# Weathe_Station.net
KiCad netlist of a schematic drawn in Altium Designer
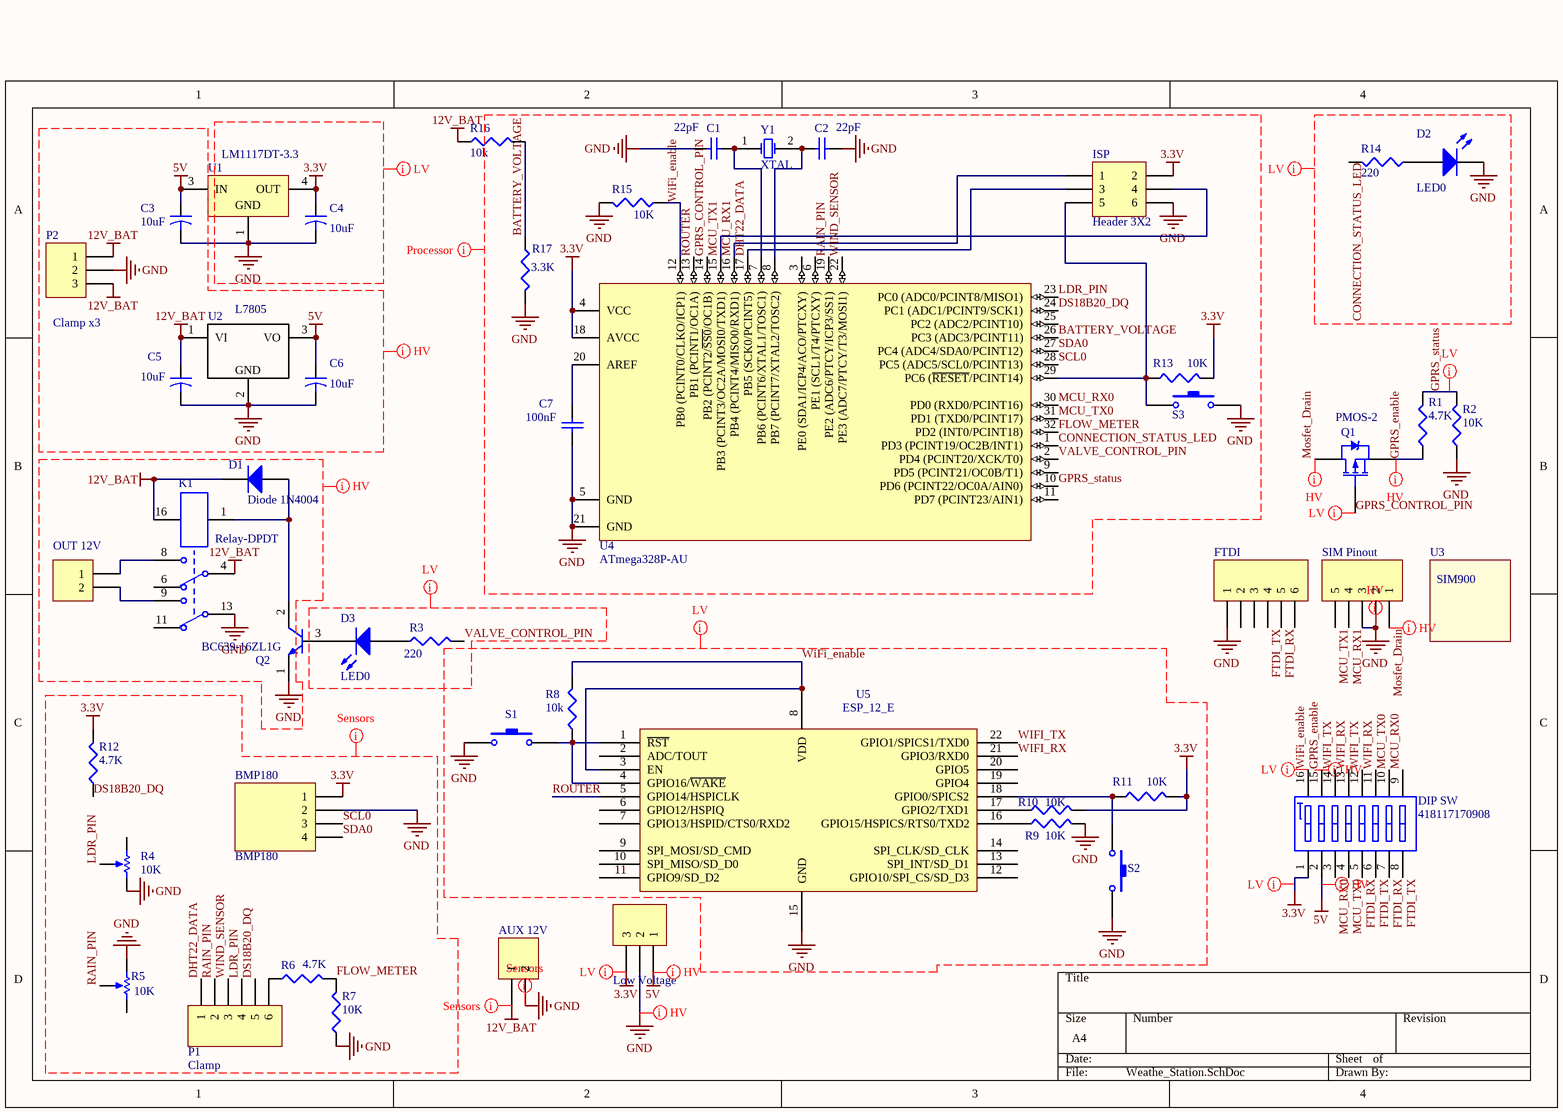
[diagram p0: Weathe_Station.SchDoc]

(export (version "E")
  (design (tool "Eeschema 10.0.6"))
  (components
    (comp (ref "AUX 12V")
      (value "AUX 12V")
      (footprint "Connector (Clamp?)")
      (description "Klema")
      (fields (field (name "PUBLISHER") "Altium Limited"))
      (libsource (lib "Connector_clamp") (part "Header 2"))
    )
    (comp (ref "BMP180")
      (value "BMP180")
      (footprint "BMP180")
      (fields (field (name "PUBLISHER") "Altium Limited"))
      (libsource (lib "BMP180") (part "BMP180"))
    )
    (comp (ref "C1")
      (value "22pF")
      (footprint "C1206")
      (description "Capacitor (Semiconductor SIM Model)")
      (fields (field (name "Comment") "Cap Semi") (field (name "PUBLISHER") "Altium Limited"))
      (libsource (lib "Miscellaneous Devices") (part "Cap Semi"))
    )
    (comp (ref "C2")
      (value "22pF")
      (footprint "C1206")
      (description "Capacitor (Semiconductor SIM Model)")
      (fields (field (name "Comment") "Cap Semi") (field (name "PUBLISHER") "Altium Limited"))
      (libsource (lib "Miscellaneous Devices") (part "Cap Semi"))
    )
    (comp (ref "C3")
      (value "10uF")
      (footprint "CAPR5-4X5")
      (description "Capacitor")
      (fields (field (name "Comment") "Cap2") (field (name "PUBLISHER") "Altium Limited"))
      (libsource (lib "Miscellaneous Devices") (part "Cap2"))
    )
    (comp (ref "C4")
      (value "10uF")
      (footprint "CAPR5-4X5")
      (description "Capacitor")
      (fields (field (name "Comment") "Cap2") (field (name "PUBLISHER") "Altium Limited"))
      (libsource (lib "Miscellaneous Devices") (part "Cap2"))
    )
    (comp (ref "C5")
      (value "10uF")
      (footprint "CAPR5-4X5")
      (description "Capacitor")
      (fields (field (name "Comment") "Cap2") (field (name "PUBLISHER") "Altium Limited"))
      (libsource (lib "Miscellaneous Devices") (part "Cap2"))
    )
    (comp (ref "C6")
      (value "10uF")
      (footprint "CAPR5-4X5")
      (description "Capacitor")
      (fields (field (name "Comment") "Cap2") (field (name "PUBLISHER") "Altium Limited"))
      (libsource (lib "Miscellaneous Devices") (part "Cap2"))
    )
    (comp (ref "C7")
      (value "100nF")
      (footprint "C1206")
      (description "Capacitor (Semiconductor SIM Model)")
      (fields (field (name "Comment") "Cap Semi") (field (name "PUBLISHER") "Altium Limited"))
      (libsource (lib "Miscellaneous Devices") (part "Cap Semi"))
    )
    (comp (ref "D1")
      (value "Diode 1N4004")
      (footprint "DO-41")
      (description "1 Amp General Purpose Rectifier")
      (fields (field (name "PUBLISHER") "Altium Limited"))
      (libsource (lib "Miscellaneous Devices") (part "Diode 1N4004"))
    )
    (comp (ref "D2")
      (value "LED0")
      (footprint "INDC3216")
      (description "SMD led")
      (fields (field (name "PUBLISHER") "Altium Limited"))
      (libsource (lib "SMD Led") (part "LED0"))
    )
    (comp (ref "D3")
      (value "LED0")
      (footprint "INDC3216")
      (description "SMD led")
      (fields (field (name "PUBLISHER") "Altium Limited"))
      (libsource (lib "SMD Led") (part "LED0"))
    )
    (comp (ref "DIP SW")
      (value "418117170908")
      (footprint "418117170908")
      (description "2.54 mm Compact THT Dip Switch with Flat Actuator WS-DITV")
      (libsource (lib "WS-DITV 2.54 mm Compact THT Dip Switch with Flat Actuator") (part "418117170908"))
    )
    (comp (ref "FTDI")
      (value "Header 6")
      (footprint "HDR1X6")
      (description "Header, 6-Pin")
      (fields (field (name "PUBLISHER") "Altium Limited"))
      (libsource (lib "Miscellaneous Connectors") (part "Header 6"))
    )
    (comp (ref "ISP")
      (value "Header 3X2")
      (footprint "HDR2X3")
      (description "Header, 3-Pin, Dual row")
      (fields (field (name "PUBLISHER") "Altium Limited"))
      (libsource (lib "Miscellaneous Connectors") (part "Header 3X2"))
    )
    (comp (ref "K1")
      (value "Relay-DPDT")
      (footprint "Sanyou Relay")
      (description "Dual-Pole Dual-Throw Relay")
      (fields (field (name "PUBLISHER") "Altium Limited"))
      (libsource (lib "Sanyou Relay") (part "Relay-DPDT"))
    )
    (comp (ref "Low Voltage")
      (value "Clamp x3")
      (footprint "Connector x3 clamps")
      (fields (field (name "PUBLISHER") "Altium Limited"))
      (libsource (lib "Connector_clamp_x3") (part "Clamp x3"))
    )
    (comp (ref "OUT 12V")
      (value "Homemade Connector")
      (footprint "Connector (Clamp?)")
      (description "Klema")
      (fields (field (name "PUBLISHER") "Altium Limited"))
      (libsource (lib "") (part "Header 2_1"))
    )
    (comp (ref "P1")
      (value "Clamp")
      (footprint "Connector Clamp (x6)")
      (description "Header, 6-Pin")
      (fields (field (name "PUBLISHER") "Altium Limited"))
      (libsource (lib "Connector_clamp_x6") (part "Header 6"))
    )
    (comp (ref "P2")
      (value "Clamp x3")
      (footprint "Connector x3 clamps")
      (fields (field (name "PUBLISHER") "Altium Limited"))
      (libsource (lib "") (part "Clamp x3_1"))
    )
    (comp (ref "Q1")
      (value "PMOS-2")
      (footprint "TO-220AB")
      (description "P-Channel Power MOSFET")
      (fields (field (name "PUBLISHER") "Altium Limited"))
      (libsource (lib "Miscellaneous Devices") (part "PMOS-2"))
    )
    (comp (ref "Q2")
      (value "BC639-16ZL1G")
      (footprint "ONSC-TO-92-3-29-11_AM_BL")
      (description "High Current Transistor, NPN Silicon, 3-Pin TO-92, Pb-Free, Ammo Box")
      (fields (field (name "MANUFACTURER") "On Semiconductor"))
      (libsource (lib "ON Semi General Purpose Transistors") (part "BC639-16ZL1G"))
    )
    (comp (ref "R1")
      (value "4.7K")
      (footprint "smd resistor 4x2mm")
      (fields (field (name "Comment") "smd resistor 4x2mm") (field (name "PUBLISHER") "Altium Limited"))
      (libsource (lib "smd resistor 4x2mm") (part "Res3"))
    )
    (comp (ref "R2")
      (value "10K")
      (footprint "smd resistor 4x2mm")
      (fields (field (name "Comment") "smd resistor 4x2mm") (field (name "PUBLISHER") "Altium Limited"))
      (libsource (lib "smd resistor 4x2mm") (part "Res3"))
    )
    (comp (ref "R3")
      (value "220")
      (footprint "smd resistor 4x2mm")
      (fields (field (name "Comment") "smd resistor 4x2mm") (field (name "PUBLISHER") "Altium Limited"))
      (libsource (lib "smd resistor 4x2mm") (part "Res3"))
    )
    (comp (ref "R4")
      (value "10K")
      (footprint "potentiometer (Piher)")
      (description "Potentiometer")
      (fields (field (name "Comment") "RPot") (field (name "PUBLISHER") "Altium Limited"))
      (libsource (lib "potentiometer (Piher)") (part "RPot"))
    )
    (comp (ref "R5")
      (value "10K")
      (footprint "potentiometer (Piher)")
      (description "Potentiometer")
      (fields (field (name "Comment") "RPot") (field (name "PUBLISHER") "Altium Limited"))
      (libsource (lib "potentiometer (Piher)") (part "RPot"))
    )
    (comp (ref "R6")
      (value "4.7K")
      (footprint "smd resistor 4x2mm")
      (fields (field (name "Comment") "smd resistor 4x2mm") (field (name "PUBLISHER") "Altium Limited"))
      (libsource (lib "smd resistor 4x2mm") (part "Res3"))
    )
    (comp (ref "R7")
      (value "10K")
      (footprint "smd resistor 4x2mm")
      (fields (field (name "Comment") "smd resistor 4x2mm") (field (name "PUBLISHER") "Altium Limited"))
      (libsource (lib "smd resistor 4x2mm") (part "Res3"))
    )
    (comp (ref "R8")
      (value "10k")
      (footprint "smd resistor 4x2mm")
      (fields (field (name "Comment") "smd resistor") (field (name "PUBLISHER") "Altium Limited"))
      (libsource (lib "smd resistor 4x2mm") (part "Res3"))
    )
    (comp (ref "R9")
      (value "10K")
      (footprint "smd resistor 4x2mm")
      (fields (field (name "Comment") "smd resistor 4x2mm") (field (name "PUBLISHER") "Altium Limited"))
      (libsource (lib "smd resistor 4x2mm") (part "Res3"))
    )
    (comp (ref "R10")
      (value "10K")
      (footprint "smd resistor 4x2mm")
      (fields (field (name "Comment") "smd resistor 4x2mm") (field (name "PUBLISHER") "Altium Limited"))
      (libsource (lib "smd resistor 4x2mm") (part "Res3"))
    )
    (comp (ref "R11")
      (value "10K")
      (footprint "smd resistor 4x2mm")
      (fields (field (name "Comment") "smd resistor 4x2mm") (field (name "PUBLISHER") "Altium Limited"))
      (libsource (lib "smd resistor 4x2mm") (part "Res3"))
    )
    (comp (ref "R12")
      (value "4.7K")
      (footprint "smd resistor 4x2mm")
      (fields (field (name "Comment") "smd resistor 4x2mm") (field (name "PUBLISHER") "Altium Limited"))
      (libsource (lib "smd resistor 4x2mm") (part "Res3"))
    )
    (comp (ref "R13")
      (value "10K")
      (footprint "smd resistor 4x2mm")
      (fields (field (name "Comment") "smd resistor 4x2mm") (field (name "PUBLISHER") "Altium Limited"))
      (libsource (lib "smd resistor 4x2mm") (part "Res3"))
    )
    (comp (ref "R14")
      (value "220")
      (footprint "smd resistor 4x2mm")
      (fields (field (name "Comment") "smd resistor 4x2mm") (field (name "PUBLISHER") "Altium Limited"))
      (libsource (lib "smd resistor 4x2mm") (part "Res3"))
    )
    (comp (ref "R15")
      (value "10K")
      (footprint "smd resistor 4x2mm")
      (fields (field (name "Comment") "smd resistor 4x2mm") (field (name "PUBLISHER") "Altium Limited"))
      (libsource (lib "smd resistor 4x2mm") (part "Res3"))
    )
    (comp (ref "R16")
      (value "10k")
      (footprint "smd resistor 4x2mm")
      (fields (field (name "Comment") "smd resistor 4x2mm") (field (name "PUBLISHER") "Altium Limited"))
      (libsource (lib "smd resistor 4x2mm") (part "Res3"))
    )
    (comp (ref "R17")
      (value "3.3K")
      (footprint "smd resistor 4x2mm")
      (fields (field (name "Comment") "smd resistor 4x2mm") (field (name "PUBLISHER") "Altium Limited"))
      (libsource (lib "smd resistor 4x2mm") (part "Res3"))
    )
    (comp (ref "S1")
      (value "SW-PB")
      (footprint "SMD push button 10x4")
      (description "Switch")
      (fields (field (name "PUBLISHER") "Altium Limited"))
      (libsource (lib "SMD push button 10x4") (part "SW-PB"))
    )
    (comp (ref "S2")
      (value "SW-PB")
      (footprint "SMD push button 10x4")
      (description "Switch")
      (fields (field (name "PUBLISHER") "Altium Limited"))
      (libsource (lib "SMD push button 10x4") (part "SW-PB"))
    )
    (comp (ref "S3")
      (value "SW-PB")
      (footprint "SMD push button 10x4")
      (description "Switch")
      (fields (field (name "PUBLISHER") "Altium Limited"))
      (libsource (lib "SMD push button 10x4") (part "SW-PB"))
    )
    (comp (ref "SIM Pinout")
      (value "Header 5")
      (footprint "HDR1X5")
      (description "Header, 5-Pin")
      (fields (field (name "PUBLISHER") "Altium Limited"))
      (libsource (lib "Miscellaneous Connectors") (part "Header 5"))
    )
    (comp (ref "U1")
      (value "LM1117DT-3.3")
      (footprint "TD03B_N")
      (description "800mA Low-Dropout Linear Regulator, 3-pin TO-252")
      (fields (field (name "MANUFACTURER") "National Semiconductor"))
      (libsource (lib "National Semiconductor LDO") (part "LM1117DT-3.3"))
    )
    (comp (ref "U2")
      (value "L7805")
      (footprint "D2PAK")
      (description "LINEAR REGULATOR 5.0V")
      (libsource (lib "vh_altium_library") (part "L7805-D2PAK"))
    )
    (comp (ref "U3") (value "SIM900") (footprint "SIM900") (libsource (lib "SIM900") (part "SIM900")))
    (comp (ref "U4")
      (value "ATmega328P-AU")
      (footprint "32A_L")
      (fields (field (name "PUBLISHER") "Altium Limited"))
      (libsource (lib "ATmega328PB") (part "ATmega328P-AU"))
    )
    (comp (ref "U5")
      (value "ESP_12_E")
      (footprint "ESP_12_E")
      (description "ESP-12 Wi-Fi Module by AI-Thinker")
      (libsource (lib "ESP8266") (part "ESP_12_E"))
    )
    (comp (ref "Y1")
      (value "XTAL")
      (footprint "R38")
      (description "Crystal Oscillator")
      (fields (field (name "PUBLISHER") "Altium Limited"))
      (libsource (lib "Miscellaneous Devices") (part "XTAL"))
    )
  )
  (nets
    (net (code "1") (name "/BATTERY_VOLTAGE") (class "Default")
      (node (ref "R16") (pin "2") (pinfunction "2_2") (pintype "passive"))
      (node (ref "R17") (pin "1") (pinfunction "1_1") (pintype "passive"))
      (node (ref "U4") (pin "26") (pinfunction "PC3_(ADC3/PCINT11)_26") (pintype "bidirectional"))
    )
    (net (code "2") (name "/CONNECTION_STATUS_LED") (class "Default")
      (node (ref "R14") (pin "2") (pinfunction "2_2") (pintype "passive"))
      (node (ref "U4") (pin "1") (pinfunction "PD3_(PCINT19/OC2B/INT1)_1") (pintype "bidirectional"))
    )
    (net (code "3") (name "/DHT22_DATA") (class "Default")
      (node (ref "ISP") (pin "3") (pinfunction "3_3") (pintype "passive"))
      (node (ref "P1") (pin "1") (pinfunction "1_1") (pintype "passive"))
      (node (ref "U4") (pin "17") (pinfunction "PB5_(SCK0/PCINT5)_17") (pintype "bidirectional"))
    )
    (net (code "4") (name "/DS18B20_DQ") (class "Default")
      (node (ref "P1") (pin "5") (pinfunction "5_5") (pintype "passive"))
      (node (ref "R12") (pin "1") (pinfunction "1_1") (pintype "passive"))
      (node (ref "U4") (pin "24") (pinfunction "PC1_(ADC1/PCINT9/SCK1)_24") (pintype "bidirectional"))
    )
    (net (code "5") (name "/FLOW_METER") (class "Default")
      (node (ref "R6") (pin "2") (pinfunction "2_2") (pintype "passive"))
      (node (ref "R7") (pin "2") (pinfunction "2_2") (pintype "passive"))
      (node (ref "U4") (pin "32") (pinfunction "PD2_(INT0/PCINT18)_32") (pintype "bidirectional"))
    )
    (net (code "6") (name "/FTDI_RX") (class "Default")
      (node (ref "DIP SW") (pin "5") (pinfunction "5_5") (pintype "passive"))
      (node (ref "DIP SW") (pin "7") (pinfunction "7_7") (pintype "passive"))
      (node (ref "FTDI") (pin "5") (pinfunction "5_5") (pintype "passive"))
    )
    (net (code "7") (name "/FTDI_TX") (class "Default")
      (node (ref "DIP SW") (pin "6") (pinfunction "6_6") (pintype "passive"))
      (node (ref "DIP SW") (pin "8") (pinfunction "8_8") (pintype "passive"))
      (node (ref "FTDI") (pin "4") (pinfunction "4_4") (pintype "passive"))
    )
    (net (code "8") (name "/GPRS_CONTROL_PIN") (class "Default")
      (node (ref "Q1") (pin "1") (pinfunction "G_1") (pintype "passive"))
      (node (ref "U4") (pin "14") (pinfunction "PB2_(PCINT2/~{SS0}/OC1B)_14") (pintype "bidirectional"))
    )
    (net (code "9") (name "/GPRS_enable") (class "Default")
      (node (ref "DIP SW") (pin "15") (pinfunction "15_15") (pintype "passive"))
      (node (ref "Q1") (pin "3") (pinfunction "S_3") (pintype "passive"))
      (node (ref "R1") (pin "1") (pinfunction "1_1") (pintype "passive"))
    )
    (net (code "10") (name "/GPRS_status") (class "Default")
      (node (ref "R1") (pin "2") (pinfunction "2_2") (pintype "passive"))
      (node (ref "R2") (pin "2") (pinfunction "2_2") (pintype "passive"))
      (node (ref "U4") (pin "10") (pinfunction "PD6_(PCINT22/OC0A/AIN0)_10") (pintype "bidirectional"))
    )
    (net (code "11") (name "/LDR_PIN") (class "Default")
      (node (ref "P1") (pin "4") (pinfunction "4_4") (pintype "passive"))
      (node (ref "R4") (pin "3") (pinfunction "TAP_3") (pintype "passive"))
      (node (ref "U4") (pin "23") (pinfunction "PC0_(ADC0/PCINT8/MISO1)_23") (pintype "bidirectional"))
    )
    (net (code "12") (name "/MCU_RX0") (class "Default")
      (node (ref "DIP SW") (pin "3") (pinfunction "3_3") (pintype "passive"))
      (node (ref "DIP SW") (pin "9") (pinfunction "9_9") (pintype "passive"))
      (node (ref "U4") (pin "30") (pinfunction "PD0_(RXD0/PCINT16)_30") (pintype "bidirectional"))
    )
    (net (code "13") (name "/MCU_RX1") (class "Default")
      (node (ref "ISP") (pin "1") (pinfunction "1_1") (pintype "passive"))
      (node (ref "SIM Pinout") (pin "4") (pinfunction "4_4") (pintype "passive"))
      (node (ref "U4") (pin "16") (pinfunction "PB4_(PCINT4/MISO0/RXD1)_16") (pintype "bidirectional"))
    )
    (net (code "14") (name "/MCU_TX0") (class "Default")
      (node (ref "DIP SW") (pin "10") (pinfunction "10_10") (pintype "passive"))
      (node (ref "DIP SW") (pin "4") (pinfunction "4_4") (pintype "passive"))
      (node (ref "U4") (pin "31") (pinfunction "PD1_(TXD0/PCINT17)_31") (pintype "bidirectional"))
    )
    (net (code "15") (name "/MCU_TX1") (class "Default")
      (node (ref "ISP") (pin "4") (pinfunction "4_4") (pintype "passive"))
      (node (ref "SIM Pinout") (pin "5") (pinfunction "5_5") (pintype "passive"))
      (node (ref "U4") (pin "15") (pinfunction "PB3_(PCINT3/OC2A/MOSI0/TXD1)_15") (pintype "bidirectional"))
    )
    (net (code "16") (name "/Mosfet_Drain") (class "Default")
      (node (ref "Q1") (pin "2") (pinfunction "D_2") (pintype "passive"))
      (node (ref "SIM Pinout") (pin "1") (pinfunction "1_1") (pintype "passive"))
    )
    (net (code "17") (name "/RAIN_PIN") (class "Default")
      (node (ref "P1") (pin "2") (pinfunction "2_2") (pintype "passive"))
      (node (ref "R5") (pin "3") (pinfunction "TAP_3") (pintype "passive"))
      (node (ref "U4") (pin "19") (pinfunction "PE2_(ADC6/PTCY/ICP3/SS1)_19") (pintype "bidirectional"))
    )
    (net (code "18") (name "/ROUTER") (class "Default")
      (node (ref "U4") (pin "13") (pinfunction "PB1_(PCINT1/OC1A)_13") (pintype "bidirectional"))
      (node (ref "U5") (pin "5") (pinfunction "GPIO14/HSPICLK_5") (pintype "passive"))
    )
    (net (code "19") (name "/SCL0") (class "Default")
      (node (ref "BMP180") (pin "3") (pinfunction "3_3") (pintype "passive"))
      (node (ref "U4") (pin "28") (pinfunction "PC5_(ADC5/SCL0/PCINT13)_28") (pintype "bidirectional"))
    )
    (net (code "20") (name "/SDA0") (class "Default")
      (node (ref "BMP180") (pin "4") (pinfunction "4_4") (pintype "passive"))
      (node (ref "U4") (pin "27") (pinfunction "PC4_(ADC4/SDA0/PCINT12)_27") (pintype "bidirectional"))
    )
    (net (code "21") (name "/VALVE_CONTROL_PIN") (class "Default")
      (node (ref "R3") (pin "2") (pinfunction "2_2") (pintype "passive"))
      (node (ref "U4") (pin "2") (pinfunction "PD4_(PCINT20/XCK/T0)_2") (pintype "bidirectional"))
    )
    (net (code "22") (name "/WIFI_RX") (class "Default")
      (node (ref "DIP SW") (pin "11") (pinfunction "11_11") (pintype "passive"))
      (node (ref "DIP SW") (pin "13") (pinfunction "13_13") (pintype "passive"))
      (node (ref "U5") (pin "21") (pinfunction "GPIO3/RXD0_21") (pintype "passive"))
    )
    (net (code "23") (name "/WIFI_TX") (class "Default")
      (node (ref "DIP SW") (pin "12") (pinfunction "12_12") (pintype "passive"))
      (node (ref "DIP SW") (pin "14") (pinfunction "14_14") (pintype "passive"))
      (node (ref "U5") (pin "22") (pinfunction "GPIO1/SPICS1/TXD0_22") (pintype "passive"))
    )
    (net (code "24") (name "/WIND_SENSOR") (class "Default")
      (node (ref "P1") (pin "3") (pinfunction "3_3") (pintype "passive"))
      (node (ref "U4") (pin "22") (pinfunction "PE3_(ADC7/PTCY/T3/MOSI1)_22") (pintype "bidirectional"))
    )
    (net (code "25") (name "/WiFi_enable") (class "Default")
      (node (ref "DIP SW") (pin "16") (pinfunction "16_16") (pintype "passive"))
      (node (ref "R15") (pin "1") (pinfunction "1_1") (pintype "passive"))
      (node (ref "R8") (pin "2") (pinfunction "2_2") (pintype "passive"))
      (node (ref "U4") (pin "12") (pinfunction "PB0_(PCINT0/CLKO/ICP1)_12") (pintype "bidirectional"))
      (node (ref "U5") (pin "3") (pinfunction "EN_3") (pintype "passive"))
      (node (ref "U5") (pin "8") (pinfunction "VDD_8") (pintype "passive"))
    )
    (net (code "26") (name "3.3V") (class "Default")
      (node (ref "BMP180") (pin "1") (pinfunction "1_1") (pintype "passive"))
      (node (ref "C4") (pin "1") (pinfunction "1_1") (pintype "passive"))
      (node (ref "DIP SW") (pin "1") (pinfunction "1_1") (pintype "passive"))
      (node (ref "ISP") (pin "2") (pinfunction "2_2") (pintype "passive"))
      (node (ref "Low Voltage") (pin "3") (pinfunction "3_3") (pintype "passive"))
      (node (ref "R10") (pin "2") (pinfunction "2_2") (pintype "passive"))
      (node (ref "R11") (pin "2") (pinfunction "2_2") (pintype "passive"))
      (node (ref "R12") (pin "2") (pinfunction "2_2") (pintype "passive"))
      (node (ref "R13") (pin "2") (pinfunction "2_2") (pintype "passive"))
      (node (ref "U1") (pin "4") (pinfunction "OUT_4") (pintype "power_in"))
      (node (ref "U4") (pin "18") (pinfunction "AVCC_18") (pintype "power_in"))
      (node (ref "U4") (pin "4") (pinfunction "VCC_4") (pintype "power_in"))
    )
    (net (code "27") (name "5V") (class "Default")
      (node (ref "C3") (pin "1") (pinfunction "1_1") (pintype "passive"))
      (node (ref "C6") (pin "1") (pinfunction "1_1") (pintype "passive"))
      (node (ref "DIP SW") (pin "2") (pinfunction "2_2") (pintype "passive"))
      (node (ref "Low Voltage") (pin "1") (pinfunction "1_1") (pintype "passive"))
      (node (ref "U1") (pin "3") (pinfunction "IN_3") (pintype "power_in"))
      (node (ref "U2") (pin "3") (pinfunction "VO_3") (pintype "passive"))
    )
    (net (code "28") (name "12V_BAT") (class "Default")
      (node (ref "AUX 12V") (pin "1") (pinfunction "1_1") (pintype "passive"))
      (node (ref "C5") (pin "1") (pinfunction "1_1") (pintype "passive"))
      (node (ref "D1") (pin "2") (pinfunction "K_2") (pintype "passive"))
      (node (ref "K1") (pin "16") (pinfunction "16_16") (pintype "passive"))
      (node (ref "K1") (pin "4") (pinfunction "4_4") (pintype "passive"))
      (node (ref "P2") (pin "1") (pinfunction "1_1") (pintype "passive"))
      (node (ref "P2") (pin "3") (pinfunction "3_3") (pintype "passive"))
      (node (ref "R16") (pin "1") (pinfunction "1_1") (pintype "passive"))
      (node (ref "U2") (pin "1") (pinfunction "VI_1") (pintype "passive"))
    )
    (net (code "29") (name "GND") (class "Default")
      (node (ref "AUX 12V") (pin "2") (pinfunction "2_2") (pintype "passive"))
      (node (ref "BMP180") (pin "2") (pinfunction "2_2") (pintype "passive"))
      (node (ref "C1") (pin "1") (pinfunction "1_1") (pintype "passive"))
      (node (ref "C2") (pin "2") (pinfunction "2_2") (pintype "passive"))
      (node (ref "C3") (pin "2") (pinfunction "2_2") (pintype "passive"))
      (node (ref "C4") (pin "2") (pinfunction "2_2") (pintype "passive"))
      (node (ref "C5") (pin "2") (pinfunction "2_2") (pintype "passive"))
      (node (ref "C6") (pin "2") (pinfunction "2_2") (pintype "passive"))
      (node (ref "C7") (pin "1") (pinfunction "1_1") (pintype "passive"))
      (node (ref "D2") (pin "2") (pinfunction "K_2") (pintype "passive"))
      (node (ref "FTDI") (pin "1") (pinfunction "1_1") (pintype "passive"))
      (node (ref "ISP") (pin "6") (pinfunction "6_6") (pintype "passive"))
      (node (ref "K1") (pin "13") (pinfunction "13_13") (pintype "passive"))
      (node (ref "Low Voltage") (pin "2") (pinfunction "2_2") (pintype "passive"))
      (node (ref "P2") (pin "2") (pinfunction "2_2") (pintype "passive"))
      (node (ref "Q2") (pin "1") (pinfunction "E_1") (pintype "passive"))
      (node (ref "R15") (pin "2") (pinfunction "2_2") (pintype "passive"))
      (node (ref "R17") (pin "2") (pinfunction "2_2") (pintype "passive"))
      (node (ref "R2") (pin "1") (pinfunction "1_1") (pintype "passive"))
      (node (ref "R4") (pin "2") (pinfunction "BOT_2") (pintype "passive"))
      (node (ref "R5") (pin "1") (pinfunction "TOP_1") (pintype "passive"))
      (node (ref "R7") (pin "1") (pinfunction "1_1") (pintype "passive"))
      (node (ref "R9") (pin "2") (pinfunction "2_2") (pintype "passive"))
      (node (ref "S1") (pin "1") (pinfunction "1_1") (pintype "passive"))
      (node (ref "S2") (pin "2") (pinfunction "2_2") (pintype "passive"))
      (node (ref "S3") (pin "2") (pinfunction "2_2") (pintype "passive"))
      (node (ref "SIM Pinout") (pin "2") (pinfunction "2_2") (pintype "passive"))
      (node (ref "SIM Pinout") (pin "3") (pinfunction "3_3") (pintype "passive"))
      (node (ref "U1") (pin "1") (pinfunction "GND_1") (pintype "power_in"))
      (node (ref "U2") (pin "2") (pintype "passive"))
      (node (ref "U4") (pin "21") (pinfunction "GND_21") (pintype "power_in"))
      (node (ref "U4") (pin "5") (pinfunction "GND_5") (pintype "power_in"))
      (node (ref "U5") (pin "15") (pinfunction "GND_15") (pintype "passive"))
    )
    (net (code "30") (name "Net-(D1-A)") (class "Default")
      (node (ref "D1") (pin "1") (pinfunction "A_1") (pintype "passive"))
      (node (ref "K1") (pin "1") (pinfunction "1_1") (pintype "passive"))
      (node (ref "Q2") (pin "2") (pinfunction "C_2") (pintype "passive"))
    )
    (net (code "31") (name "Net-(D2-A)") (class "Default")
      (node (ref "D2") (pin "1") (pinfunction "A_1") (pintype "passive"))
      (node (ref "R14") (pin "1") (pinfunction "1_1") (pintype "passive"))
    )
    (net (code "32") (name "Net-(D3-A)") (class "Default")
      (node (ref "D3") (pin "1") (pinfunction "A_1") (pintype "passive"))
      (node (ref "R3") (pin "1") (pinfunction "1_1") (pintype "passive"))
    )
    (net (code "33") (name "Net-(D3-K)") (class "Default")
      (node (ref "D3") (pin "2") (pinfunction "K_2") (pintype "passive"))
      (node (ref "Q2") (pin "3") (pinfunction "B_3") (pintype "passive"))
    )
    (net (code "34") (name "Net-(K1-Pad8)") (class "Default")
      (node (ref "K1") (pin "8") (pinfunction "8_8") (pintype "passive"))
      (node (ref "OUT 12V") (pin "1") (pinfunction "1_1") (pintype "passive"))
    )
    (net (code "35") (name "Net-(K1-Pad9)") (class "Default")
      (node (ref "K1") (pin "9") (pinfunction "9_9") (pintype "passive"))
      (node (ref "OUT 12V") (pin "2") (pinfunction "2_2") (pintype "passive"))
    )
    (net (code "36") (name "Net-(P1-Pad6)") (class "Default")
      (node (ref "P1") (pin "6") (pinfunction "6_6") (pintype "passive"))
      (node (ref "R6") (pin "1") (pinfunction "1_1") (pintype "passive"))
    )
    (net (code "37") (name "Net-(U4-AREF)") (class "Default")
      (node (ref "C7") (pin "2") (pinfunction "2_2") (pintype "passive"))
      (node (ref "U4") (pin "20") (pinfunction "AREF_20") (pintype "passive"))
    )
    (net (code "38") (name "Net-(U4-PB6_(PCINT6{slash}XTAL1{slash}TOSC1))") (class "Default")
      (node (ref "C1") (pin "2") (pinfunction "2_2") (pintype "passive"))
      (node (ref "U4") (pin "7") (pinfunction "PB6_(PCINT6/XTAL1/TOSC1)_7") (pintype "bidirectional"))
      (node (ref "Y1") (pin "1") (pinfunction "OSC1_1") (pintype "passive"))
    )
    (net (code "39") (name "Net-(U4-PB7_(PCINT7{slash}XTAL2{slash}TOSC2))") (class "Default")
      (node (ref "C2") (pin "1") (pinfunction "1_1") (pintype "passive"))
      (node (ref "U4") (pin "8") (pinfunction "PB7_(PCINT7/XTAL2/TOSC2)_8") (pintype "bidirectional"))
      (node (ref "Y1") (pin "2") (pinfunction "OSC2_2") (pintype "passive"))
    )
    (net (code "40") (name "Net-(U4-PC6_(~{RESET}{slash}PCINT14))") (class "Default")
      (node (ref "ISP") (pin "5") (pinfunction "5_5") (pintype "passive"))
      (node (ref "R13") (pin "1") (pinfunction "1_1") (pintype "passive"))
      (node (ref "S3") (pin "1") (pinfunction "1_1") (pintype "passive"))
      (node (ref "U4") (pin "29") (pinfunction "PC6_(~{RESET}/PCINT14)_29") (pintype "bidirectional"))
    )
    (net (code "41") (name "Net-(U5-GPIO0{slash}SPICS2)") (class "Default")
      (node (ref "R11") (pin "1") (pinfunction "1_1") (pintype "passive"))
      (node (ref "S2") (pin "1") (pinfunction "1_1") (pintype "passive"))
      (node (ref "U5") (pin "18") (pinfunction "GPIO0/SPICS2_18") (pintype "passive"))
    )
    (net (code "42") (name "Net-(U5-GPIO2{slash}TXD1)") (class "Default")
      (node (ref "R10") (pin "1") (pinfunction "1_1") (pintype "passive"))
      (node (ref "U5") (pin "17") (pinfunction "GPIO2/TXD1_17") (pintype "passive"))
    )
    (net (code "43") (name "Net-(U5-GPIO15{slash}HSPICS{slash}RTS0{slash}TXD2)") (class "Default")
      (node (ref "R9") (pin "1") (pinfunction "1_1") (pintype "passive"))
      (node (ref "U5") (pin "16") (pinfunction "GPIO15/HSPICS/RTS0/TXD2_16") (pintype "passive"))
    )
    (net (code "44") (name "Net-(U5-GPIO16{slash}~{WAKE})") (class "Default")
      (node (ref "R8") (pin "1") (pinfunction "1_1") (pintype "passive"))
      (node (ref "S1") (pin "2") (pinfunction "2_2") (pintype "passive"))
      (node (ref "U5") (pin "1") (pinfunction "~{RST}_1") (pintype "passive"))
      (node (ref "U5") (pin "4") (pinfunction "GPIO16/~{WAKE}_4") (pintype "passive"))
    )
    (net (code "45") (name "unconnected-(FTDI-Pad2)") (class "Default")
      (node (ref "FTDI") (pin "2") (pinfunction "2_2") (pintype "passive"))
    )
    (net (code "46") (name "unconnected-(FTDI-Pad3)") (class "Default")
      (node (ref "FTDI") (pin "3") (pinfunction "3_3") (pintype "passive"))
    )
    (net (code "47") (name "unconnected-(FTDI-Pad6)") (class "Default")
      (node (ref "FTDI") (pin "6") (pinfunction "6_6") (pintype "passive"))
    )
    (net (code "48") (name "unconnected-(K1-Pad6)") (class "Default")
      (node (ref "K1") (pin "6") (pinfunction "6_6") (pintype "passive"))
    )
    (net (code "49") (name "unconnected-(K1-Pad11)") (class "Default")
      (node (ref "K1") (pin "11") (pinfunction "11_11") (pintype "passive"))
    )
    (net (code "50") (name "unconnected-(R4-TOP-Pad1)") (class "Default")
      (node (ref "R4") (pin "1") (pinfunction "TOP_1") (pintype "passive"))
    )
    (net (code "51") (name "unconnected-(R5-BOT-Pad2)") (class "Default")
      (node (ref "R5") (pin "2") (pinfunction "BOT_2") (pintype "passive"))
    )
    (net (code "52") (name "unconnected-(U4-PC2_(ADC2{slash}PCINT10)-Pad25)") (class "Default")
      (node (ref "U4") (pin "25") (pinfunction "PC2_(ADC2/PCINT10)_25") (pintype "bidirectional"))
    )
    (net (code "53") (name "unconnected-(U4-PD5_(PCINT21{slash}OC0B{slash}T1)-Pad9)") (class "Default")
      (node (ref "U4") (pin "9") (pinfunction "PD5_(PCINT21/OC0B/T1)_9") (pintype "bidirectional"))
    )
    (net (code "54") (name "unconnected-(U4-PD7_(PCINT23{slash}AIN1)-Pad11)") (class "Default")
      (node (ref "U4") (pin "11") (pinfunction "PD7_(PCINT23/AIN1)_11") (pintype "bidirectional"))
    )
    (net (code "55") (name "unconnected-(U4-PE0_(SDA1{slash}ICP4{slash}ACO{slash}PTCXY)-Pad3)") (class "Default")
      (node (ref "U4") (pin "3") (pinfunction "PE0_(SDA1/ICP4/ACO/PTCXY)_3") (pintype "bidirectional"))
    )
    (net (code "56") (name "unconnected-(U4-PE1_(SCL1{slash}T4{slash}PTCXY)-Pad6)") (class "Default")
      (node (ref "U4") (pin "6") (pinfunction "PE1_(SCL1/T4/PTCXY)_6") (pintype "bidirectional"))
    )
    (net (code "57") (name "unconnected-(U5-ADC{slash}TOUT-Pad2)") (class "Default")
      (node (ref "U5") (pin "2") (pinfunction "ADC/TOUT_2") (pintype "passive"))
    )
    (net (code "58") (name "unconnected-(U5-GPIO4-Pad19)") (class "Default")
      (node (ref "U5") (pin "19") (pinfunction "GPIO4_19") (pintype "passive"))
    )
    (net (code "59") (name "unconnected-(U5-GPIO5-Pad20)") (class "Default")
      (node (ref "U5") (pin "20") (pinfunction "GPIO5_20") (pintype "passive"))
    )
    (net (code "60") (name "unconnected-(U5-GPIO9{slash}SD_D2-Pad11)") (class "Default")
      (node (ref "U5") (pin "11") (pinfunction "GPIO9/SD_D2_11") (pintype "passive"))
    )
    (net (code "61") (name "unconnected-(U5-GPIO10{slash}SPI_CS{slash}SD_D3-Pad12)") (class "Default")
      (node (ref "U5") (pin "12") (pinfunction "GPIO10/SPI_CS/SD_D3_12") (pintype "passive"))
    )
    (net (code "62") (name "unconnected-(U5-GPIO12{slash}HSPIQ-Pad6)") (class "Default")
      (node (ref "U5") (pin "6") (pinfunction "GPIO12/HSPIQ_6") (pintype "passive"))
    )
    (net (code "63") (name "unconnected-(U5-GPIO13{slash}HSPID{slash}CTS0{slash}RXD2-Pad7)") (class "Default")
      (node (ref "U5") (pin "7") (pinfunction "GPIO13/HSPID/CTS0/RXD2_7") (pintype "passive"))
    )
    (net (code "64") (name "unconnected-(U5-SPI_CLK{slash}SD_CLK-Pad14)") (class "Default")
      (node (ref "U5") (pin "14") (pinfunction "SPI_CLK/SD_CLK_14") (pintype "passive"))
    )
    (net (code "65") (name "unconnected-(U5-SPI_INT{slash}SD_D1-Pad13)") (class "Default")
      (node (ref "U5") (pin "13") (pinfunction "SPI_INT/SD_D1_13") (pintype "passive"))
    )
    (net (code "66") (name "unconnected-(U5-SPI_MISO{slash}SD_D0-Pad10)") (class "Default")
      (node (ref "U5") (pin "10") (pinfunction "SPI_MISO/SD_D0_10") (pintype "passive"))
    )
    (net (code "67") (name "unconnected-(U5-SPI_MOSI{slash}SD_CMD-Pad9)") (class "Default")
      (node (ref "U5") (pin "9") (pinfunction "SPI_MOSI/SD_CMD_9") (pintype "passive"))
    )
  )
)
